# ps2amiga.net
KiCad netlist of a schematic drawn in EAGLE
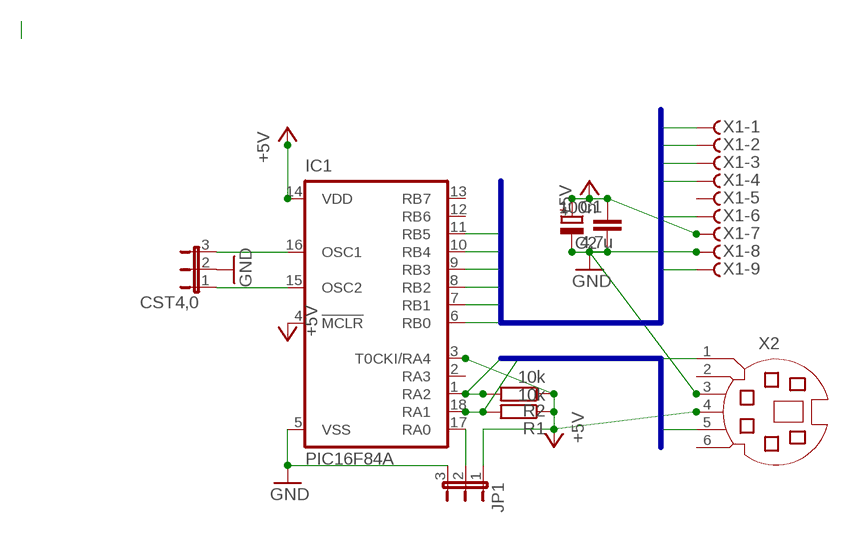
[diagram p0: schematic, sheet 1]

(export (version "E")
  (design (tool "Eeschema 10.0.6"))
  (components
    (comp (ref "C1")
      (value "4,7u")
      (footprint "eagle-import:E2,5-6")
      (libsource (lib "eagle-import") (part "CPOL-EUE2.5-6"))
    )
    (comp (ref "C2")
      (value "100n")
      (footprint "eagle-import:C025-025X050")
      (libsource (lib "eagle-import") (part "C-EU025-025X050"))
    )
    (comp (ref "CST4,0")
      (value "JP2E")
      (footprint "eagle-import:JP2")
      (libsource (lib "eagle-import") (part "JP2E"))
    )
    (comp (ref "IC1")
      (value "PIC16F84A")
      (footprint "eagle-import:DIL18")
      (libsource (lib "eagle-import") (part "PIC16C84P"))
    )
    (comp (ref "JP1")
      (value "JP2E")
      (footprint "eagle-import:JP2")
      (libsource (lib "eagle-import") (part "JP2E"))
    )
    (comp (ref "R1")
      (value "10k")
      (footprint "eagle-import:0207_10")
      (libsource (lib "eagle-import") (part "R-EU_0207/10"))
    )
    (comp (ref "R2")
      (value "10k")
      (footprint "eagle-import:0207_10")
      (libsource (lib "eagle-import") (part "R-EU_0207/10"))
    )
    (comp (ref "X1")
      (value "F09HS")
      (footprint "eagle-import:F09H")
      (libsource (lib "eagle-import") (part "F09?SH"))
    )
    (comp (ref "X2")
      (value "MD06S")
      (footprint "eagle-import:MDIN06S")
      (libsource (lib "eagle-import") (part "MD06S"))
    )
  )
  (nets
    (net (code "1") (name "+5V") (class "Default")
      (node (ref "C1") (pin "+") (pinfunction "+_+") (pintype "passive"))
      (node (ref "C2") (pin "2") (pinfunction "2_2") (pintype "passive"))
      (node (ref "IC1") (pin "14") (pinfunction "VDD_14") (pintype "power_in"))
      (node (ref "IC1") (pin "3") (pinfunction "T0CKI/RA4_3") (pintype "bidirectional"))
      (node (ref "IC1") (pin "4") (pinfunction "~{MCLR}_4") (pintype "input"))
      (node (ref "JP1") (pin "1") (pinfunction "1_1") (pintype "passive"))
      (node (ref "R1") (pin "1") (pinfunction "1_1") (pintype "passive"))
      (node (ref "R2") (pin "1") (pinfunction "1_1") (pintype "passive"))
      (node (ref "X1") (pin "7") (pinfunction "F_7") (pintype "passive"))
      (node (ref "X2") (pin "4") (pinfunction "4_4") (pintype "passive"))
    )
    (net (code "2") (name "/A1") (class "Default")
      (node (ref "IC1") (pin "7") (pinfunction "RB1_7") (pintype "bidirectional"))
      (node (ref "X1") (pin "1") (pinfunction "F_1") (pintype "passive"))
    )
    (net (code "3") (name "/A2") (class "Default")
      (node (ref "IC1") (pin "6") (pinfunction "RB0_6") (pintype "bidirectional"))
      (node (ref "X1") (pin "2") (pinfunction "F_2") (pintype "passive"))
    )
    (net (code "4") (name "/A3") (class "Default")
      (node (ref "IC1") (pin "8") (pinfunction "RB2_8") (pintype "bidirectional"))
      (node (ref "X1") (pin "3") (pinfunction "F_3") (pintype "passive"))
    )
    (net (code "5") (name "/A4") (class "Default")
      (node (ref "IC1") (pin "9") (pinfunction "RB3_9") (pintype "bidirectional"))
      (node (ref "X1") (pin "4") (pinfunction "F_4") (pintype "passive"))
    )
    (net (code "6") (name "/A5") (class "Default")
      (node (ref "IC1") (pin "11") (pinfunction "RB5_11") (pintype "bidirectional"))
      (node (ref "X1") (pin "9") (pinfunction "F_9") (pintype "passive"))
    )
    (net (code "7") (name "/A6") (class "Default")
      (node (ref "IC1") (pin "10") (pinfunction "RB4_10") (pintype "bidirectional"))
      (node (ref "X1") (pin "6") (pinfunction "F_6") (pintype "passive"))
    )
    (net (code "8") (name "/B1") (class "Default")
      (node (ref "IC1") (pin "18") (pinfunction "RA1_18") (pintype "bidirectional"))
      (node (ref "R1") (pin "2") (pinfunction "2_2") (pintype "passive"))
      (node (ref "X2") (pin "1") (pinfunction "1_1") (pintype "passive"))
    )
    (net (code "9") (name "/B2") (class "Default")
      (node (ref "IC1") (pin "1") (pinfunction "RA2_1") (pintype "bidirectional"))
      (node (ref "R2") (pin "2") (pinfunction "2_2") (pintype "passive"))
      (node (ref "X2") (pin "5") (pinfunction "5_5") (pintype "passive"))
    )
    (net (code "10") (name "GND") (class "Default")
      (node (ref "C1") (pin "-") (pinfunction "-_-") (pintype "passive"))
      (node (ref "C2") (pin "1") (pinfunction "1_1") (pintype "passive"))
      (node (ref "CST4,0") (pin "2") (pinfunction "2_2") (pintype "passive"))
      (node (ref "IC1") (pin "5") (pinfunction "VSS_5") (pintype "power_in"))
      (node (ref "JP1") (pin "3") (pinfunction "3_3") (pintype "passive"))
      (node (ref "X1") (pin "8") (pinfunction "F_8") (pintype "passive"))
      (node (ref "X2") (pin "3") (pinfunction "3_3") (pintype "passive"))
    )
    (net (code "11") (name "Net-(IC1-OSC1)") (class "Default")
      (node (ref "CST4,0") (pin "3") (pinfunction "3_3") (pintype "passive"))
      (node (ref "IC1") (pin "16") (pinfunction "OSC1_16") (pintype "input"))
    )
    (net (code "12") (name "Net-(IC1-OSC2)") (class "Default")
      (node (ref "CST4,0") (pin "1") (pinfunction "1_1") (pintype "passive"))
      (node (ref "IC1") (pin "15") (pinfunction "OSC2_15") (pintype "output"))
    )
    (net (code "13") (name "Net-(IC1-RA0)") (class "Default")
      (node (ref "IC1") (pin "17") (pinfunction "RA0_17") (pintype "bidirectional"))
      (node (ref "JP1") (pin "2") (pinfunction "2_2") (pintype "passive"))
    )
    (net (code "14") (name "unconnected-(IC1-RA3-Pad2)") (class "Default")
      (node (ref "IC1") (pin "2") (pinfunction "RA3_2") (pintype "bidirectional"))
    )
    (net (code "15") (name "unconnected-(IC1-RB6-Pad12)") (class "Default")
      (node (ref "IC1") (pin "12") (pinfunction "RB6_12") (pintype "bidirectional"))
    )
    (net (code "16") (name "unconnected-(IC1-RB7-Pad13)") (class "Default")
      (node (ref "IC1") (pin "13") (pinfunction "RB7_13") (pintype "bidirectional"))
    )
    (net (code "17") (name "unconnected-(X1E-F-Pad5)") (class "Default")
      (node (ref "X1") (pin "5") (pinfunction "F_5") (pintype "passive"))
    )
    (net (code "18") (name "unconnected-(X2-Pad2)") (class "Default")
      (node (ref "X2") (pin "2") (pinfunction "2_2") (pintype "passive"))
    )
    (net (code "19") (name "unconnected-(X2-Pad6)") (class "Default")
      (node (ref "X2") (pin "6") (pinfunction "6_6") (pintype "passive"))
    )
  )
)
